# RFR24_AMS_Design_-_Microcontroller_V1.net
KiCad netlist of a schematic drawn in Altium Designer
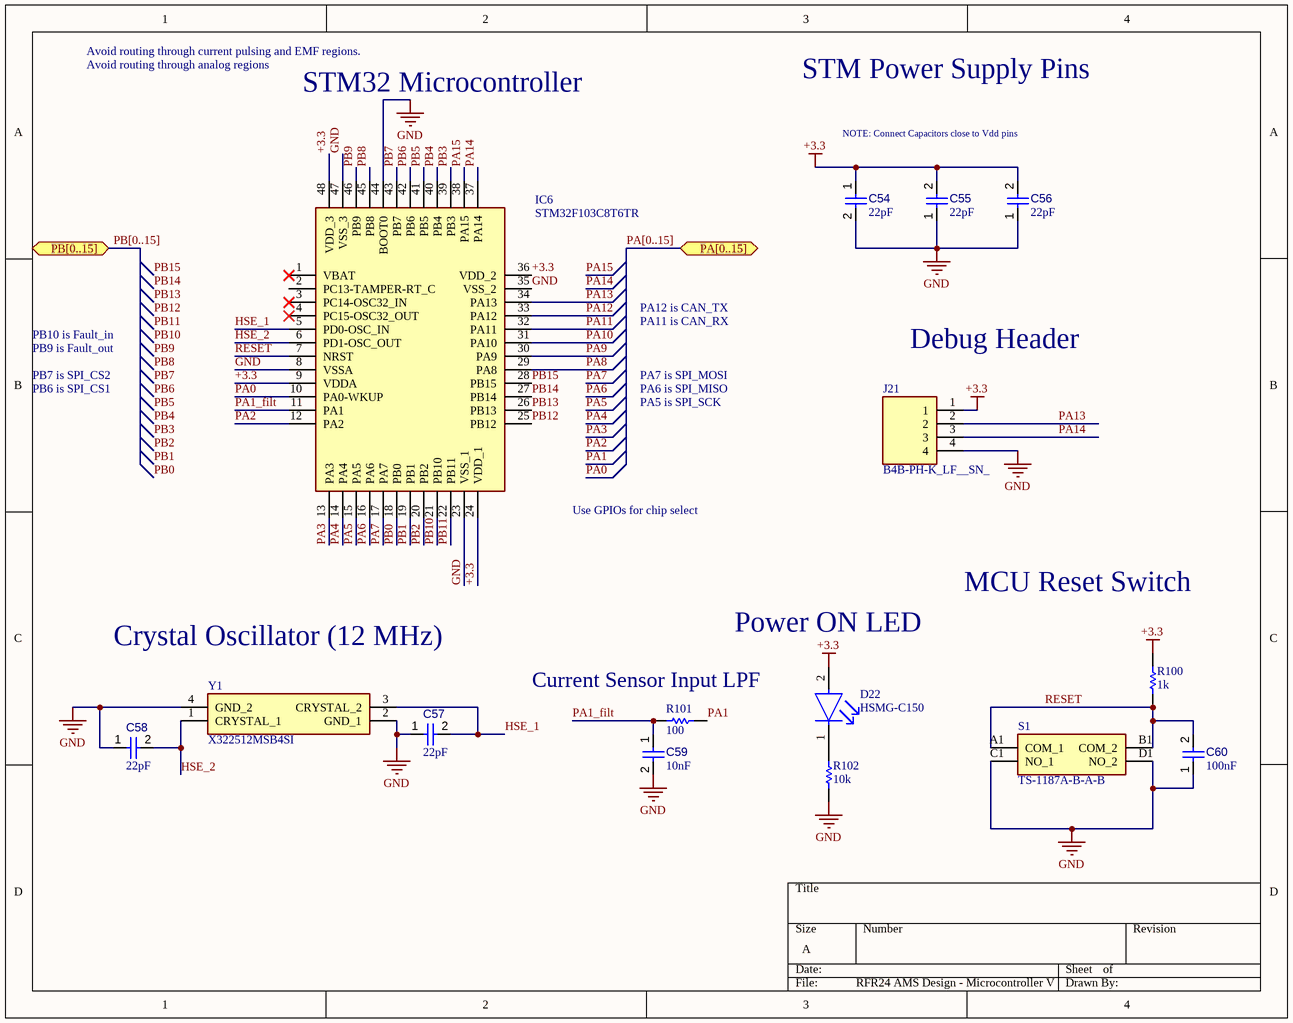
[diagram p0: RFR24 AMS Design - Microcontroller V1.SchDoc]

(export (version "E")
  (design (tool "Eeschema 10.0.6"))
  (components
    (comp (ref "C54")
      (value "22pF")
      (footprint "CAPC2013X145X50LL20T25")
      (description "Chip Capacitor, 1 uF, +/-10%, 25 V, 0805 (2012 Metric)")
      (fields (field (name "TOLERANCE") "10%") (field (name "Comment") "Capacitor 1 uF +/- 10% 25 V 0805"))
      (libsource (lib "Rutgers University") (part "CAP-NP-2"))
    )
    (comp (ref "C55")
      (value "22pF")
      (footprint "CAPC2013X145X50LL20T25")
      (description "Chip Capacitor, 1 uF, +/-10%, 25 V, 0805 (2012 Metric)")
      (fields (field (name "TOLERANCE") "10%") (field (name "Comment") "Capacitor 1 uF +/- 10% 25 V 0805"))
      (libsource (lib "Rutgers University") (part "CAP-NP-2"))
    )
    (comp (ref "C56")
      (value "22pF")
      (footprint "CAPC2013X145X50LL20T25")
      (description "Chip Capacitor, 1 uF, +/-10%, 25 V, 0805 (2012 Metric)")
      (fields (field (name "TOLERANCE") "10%") (field (name "Comment") "Capacitor 1 uF +/- 10% 25 V 0805"))
      (libsource (lib "Rutgers University") (part "CAP-NP-2"))
    )
    (comp (ref "C57")
      (value "22pF")
      (footprint "CAPC2013X145X50LL20T25")
      (description "Chip Capacitor, 1 uF, +/-10%, 25 V, 0805 (2012 Metric)")
      (fields (field (name "TOLERANCE") "10%") (field (name "Comment") "Capacitor 1 uF +/- 10% 25 V 0805"))
      (libsource (lib "Rutgers University") (part "CAP-NP-2"))
    )
    (comp (ref "C58")
      (value "22pF")
      (footprint "CAPC2013X145X50LL20T25")
      (description "Chip Capacitor, 1 uF, +/-10%, 25 V, 0805 (2012 Metric)")
      (fields (field (name "TOLERANCE") "10%") (field (name "Comment") "Capacitor 1 uF +/- 10% 25 V 0805"))
      (libsource (lib "Rutgers University") (part "CAP-NP-2"))
    )
    (comp (ref "C59")
      (value "10nF")
      (footprint "CAPC2013X145X50LL20T25")
      (description "Chip Capacitor, 1 uF, +/-10%, 25 V, 0805 (2012 Metric)")
      (fields (field (name "TOLERANCE") "10%") (field (name "Comment") "Capacitor 1 uF +/- 10% 25 V 0805"))
      (libsource (lib "Rutgers University") (part "CAP-NP-2"))
    )
    (comp (ref "C60")
      (value "100nF")
      (footprint "CAPC2013X145X50LL20T25")
      (description "Chip Capacitor, 1 uF, +/-10%, 25 V, 0805 (2012 Metric)")
      (fields (field (name "TOLERANCE") "10%") (field (name "Comment") "Capacitor 1 uF +/- 10% 25 V 0805"))
      (libsource (lib "Rutgers University") (part "CAP-NP-2"))
    )
    (comp (ref "D22")
      (value "HSMG-C150")
      (footprint "FP-HSMG-C150-MFG")
      (description "LED GREEN DIFFUSED 1206 SMD")
      (fields
        (field (name "MANUFACTURER") "Broadcom")
        (field (name "OCTOPART") "https://octopart.com/hsmg-c150-broadcom-71131304")
      )
      (libsource (lib "Altium Content Vault") (part "8706943c75ba83719d021d2fdc84c58"))
    )
    (comp (ref "IC6")
      (value "STM32F103C8T6TR")
      (footprint "SamacSys:QFP50P900X900X160-48N")
      (description "Integrated Circuit")
      (fields (field (name "MOUSER PART NUMBER") "511-STM32F103C8T6TR"))
      (libsource (lib "*") (part "STM32F103C8T6TR"))
    )
    (comp (ref "J21")
      (value "B4B-PH-K_LF__SN_")
      (footprint "SamacSys:SHDR4W50P0X200_1X4_990X450X600P")
      (description "Connector")
      (fields (field (name "MANUFACTURER_PART_NUMBER") "B4B-PH-K(LF)(SN)"))
      (libsource (lib "*") (part "B4B-PH-K_LF__SN_"))
    )
    (comp (ref "R100")
      (value "1k")
      (footprint "RESC2013X70X40LL20T20")
      (description "Chip Resistor, 1 KOhm, +/- 1%, 0.125 W, -55 to 155 degC, 0805 (2013 Metric)")
      (fields (field (name "TOLERANCE") "1%") (field (name "POWER") "125mW"))
      (libsource (lib "Rutgers University") (part "RES-2"))
    )
    (comp (ref "R101")
      (value "100")
      (footprint "RESC2013X70X40LL20T20")
      (description "Chip Resistor, 1 KOhm, +/- 1%, 0.125 W, -55 to 155 degC, 0805 (2013 Metric)")
      (fields (field (name "TOLERANCE") "1%") (field (name "POWER") "125mW"))
      (libsource (lib "Rutgers University") (part "RES-2"))
    )
    (comp (ref "R102")
      (value "10k")
      (footprint "RESC2013X70X40LL20T20")
      (description "Chip Resistor, 1 KOhm, +/- 1%, 0.125 W, -55 to 155 degC, 0805 (2013 Metric)")
      (fields (field (name "TOLERANCE") "1%") (field (name "POWER") "125mW"))
      (libsource (lib "Rutgers University") (part "RES-2"))
    )
    (comp (ref "S1")
      (value "TS-1187A-B-A-B")
      (footprint "SamacSys:TS1187ABAB")
      (description "Switch")
      (libsource (lib "*") (part "TS-1187A-B-A-B"))
    )
    (comp (ref "Y1")
      (value "X322512MSB4SI")
      (footprint "SamacSys:X322512MSB4SI")
      (description "Crystal or Oscillator")
      (libsource (lib "*") (part "X322512MSB4SI"))
    )
  )
  (nets
    (net (code "1") (name "+3.3") (class "Default")
      (node (ref "C54") (pin "1") (pinfunction "1_1") (pintype "passive"))
      (node (ref "C55") (pin "2") (pinfunction "2_2") (pintype "passive"))
      (node (ref "C56") (pin "2") (pinfunction "2_2") (pintype "passive"))
      (node (ref "D22") (pin "2") (pinfunction "A_2") (pintype "passive"))
      (node (ref "IC6") (pin "24") (pinfunction "VDD_1_24") (pintype "passive"))
      (node (ref "IC6") (pin "36") (pinfunction "VDD_2_36") (pintype "passive"))
      (node (ref "IC6") (pin "48") (pinfunction "VDD_3_48") (pintype "passive"))
      (node (ref "IC6") (pin "9") (pinfunction "VDDA_9") (pintype "passive"))
      (node (ref "J21") (pin "1") (pinfunction "1_1") (pintype "passive"))
      (node (ref "R100") (pin "2") (pinfunction "2_2") (pintype "passive"))
    )
    (net (code "2") (name "/HSE_1") (class "Default")
      (node (ref "C57") (pin "2") (pinfunction "2_2") (pintype "passive"))
      (node (ref "IC6") (pin "5") (pinfunction "PD0-OSC_IN_5") (pintype "passive"))
      (node (ref "Y1") (pin "3") (pinfunction "CRYSTAL_2_3") (pintype "passive"))
    )
    (net (code "3") (name "/HSE_2") (class "Default")
      (node (ref "C58") (pin "2") (pinfunction "2_2") (pintype "passive"))
      (node (ref "IC6") (pin "6") (pinfunction "PD1-OSC_OUT_6") (pintype "passive"))
      (node (ref "Y1") (pin "1") (pinfunction "CRYSTAL_1_1") (pintype "passive"))
    )
    (net (code "4") (name "/PA0") (class "Default")
      (node (ref "IC6") (pin "10") (pinfunction "PA0-WKUP_10") (pintype "passive"))
    )
    (net (code "5") (name "/PA1") (class "Default")
      (node (ref "R101") (pin "1") (pinfunction "1_1") (pintype "passive"))
    )
    (net (code "6") (name "/PA1_filt") (class "Default")
      (node (ref "C59") (pin "1") (pinfunction "1_1") (pintype "passive"))
      (node (ref "IC6") (pin "11") (pinfunction "PA1_11") (pintype "passive"))
      (node (ref "R101") (pin "2") (pinfunction "2_2") (pintype "passive"))
    )
    (net (code "7") (name "/PA2") (class "Default")
      (node (ref "IC6") (pin "12") (pinfunction "PA2_12") (pintype "passive"))
    )
    (net (code "8") (name "/PA3") (class "Default")
      (node (ref "IC6") (pin "13") (pinfunction "PA3_13") (pintype "passive"))
    )
    (net (code "9") (name "/PA4") (class "Default")
      (node (ref "IC6") (pin "14") (pinfunction "PA4_14") (pintype "passive"))
    )
    (net (code "10") (name "/PA5") (class "Default")
      (node (ref "IC6") (pin "15") (pinfunction "PA5_15") (pintype "passive"))
    )
    (net (code "11") (name "/PA6") (class "Default")
      (node (ref "IC6") (pin "16") (pinfunction "PA6_16") (pintype "passive"))
    )
    (net (code "12") (name "/PA7") (class "Default")
      (node (ref "IC6") (pin "17") (pinfunction "PA7_17") (pintype "passive"))
    )
    (net (code "13") (name "/PA8") (class "Default")
      (node (ref "IC6") (pin "29") (pinfunction "PA8_29") (pintype "passive"))
    )
    (net (code "14") (name "/PA9") (class "Default")
      (node (ref "IC6") (pin "30") (pinfunction "PA9_30") (pintype "passive"))
    )
    (net (code "15") (name "/PA10") (class "Default")
      (node (ref "IC6") (pin "31") (pinfunction "PA10_31") (pintype "passive"))
    )
    (net (code "16") (name "/PA11") (class "Default")
      (node (ref "IC6") (pin "32") (pinfunction "PA11_32") (pintype "passive"))
    )
    (net (code "17") (name "/PA12") (class "Default")
      (node (ref "IC6") (pin "33") (pinfunction "PA12_33") (pintype "passive"))
    )
    (net (code "18") (name "/PA13") (class "Default")
      (node (ref "IC6") (pin "34") (pinfunction "PA13_34") (pintype "passive"))
      (node (ref "J21") (pin "2") (pinfunction "2_2") (pintype "passive"))
    )
    (net (code "19") (name "/PA14") (class "Default")
      (node (ref "IC6") (pin "37") (pinfunction "PA14_37") (pintype "passive"))
      (node (ref "J21") (pin "3") (pinfunction "3_3") (pintype "passive"))
    )
    (net (code "20") (name "/PA15") (class "Default")
      (node (ref "IC6") (pin "38") (pinfunction "PA15_38") (pintype "passive"))
    )
    (net (code "22") (name "/PB0") (class "Default")
      (node (ref "IC6") (pin "18") (pinfunction "PB0_18") (pintype "passive"))
    )
    (net (code "23") (name "/PB1") (class "Default")
      (node (ref "IC6") (pin "19") (pinfunction "PB1_19") (pintype "passive"))
    )
    (net (code "24") (name "/PB2") (class "Default")
      (node (ref "IC6") (pin "20") (pinfunction "PB2_20") (pintype "passive"))
    )
    (net (code "25") (name "/PB3") (class "Default")
      (node (ref "IC6") (pin "39") (pinfunction "PB3_39") (pintype "passive"))
    )
    (net (code "26") (name "/PB4") (class "Default")
      (node (ref "IC6") (pin "40") (pinfunction "PB4_40") (pintype "passive"))
    )
    (net (code "27") (name "/PB5") (class "Default")
      (node (ref "IC6") (pin "41") (pinfunction "PB5_41") (pintype "passive"))
    )
    (net (code "28") (name "/PB6") (class "Default")
      (node (ref "IC6") (pin "42") (pinfunction "PB6_42") (pintype "passive"))
    )
    (net (code "29") (name "/PB7") (class "Default")
      (node (ref "IC6") (pin "43") (pinfunction "PB7_43") (pintype "passive"))
    )
    (net (code "30") (name "/PB8") (class "Default")
      (node (ref "IC6") (pin "45") (pinfunction "PB8_45") (pintype "passive"))
    )
    (net (code "31") (name "/PB9") (class "Default")
      (node (ref "IC6") (pin "46") (pinfunction "PB9_46") (pintype "passive"))
    )
    (net (code "32") (name "/PB10") (class "Default")
      (node (ref "IC6") (pin "21") (pinfunction "PB10_21") (pintype "passive"))
    )
    (net (code "33") (name "/PB11") (class "Default")
      (node (ref "IC6") (pin "22") (pinfunction "PB11_22") (pintype "passive"))
    )
    (net (code "34") (name "/PB12") (class "Default")
      (node (ref "IC6") (pin "25") (pinfunction "PB12_25") (pintype "passive"))
    )
    (net (code "35") (name "/PB13") (class "Default")
      (node (ref "IC6") (pin "26") (pinfunction "PB13_26") (pintype "passive"))
    )
    (net (code "36") (name "/PB14") (class "Default")
      (node (ref "IC6") (pin "27") (pinfunction "PB14_27") (pintype "passive"))
    )
    (net (code "37") (name "/PB15") (class "Default")
      (node (ref "IC6") (pin "28") (pinfunction "PB15_28") (pintype "passive"))
    )
    (net (code "39") (name "/RESET") (class "Default")
      (node (ref "C60") (pin "2") (pinfunction "2_2") (pintype "passive"))
      (node (ref "IC6") (pin "7") (pinfunction "NRST_7") (pintype "passive"))
      (node (ref "R100") (pin "1") (pinfunction "1_1") (pintype "passive"))
      (node (ref "S1") (pin "A1") (pinfunction "COM_1_A1") (pintype "passive"))
      (node (ref "S1") (pin "B1") (pinfunction "COM_2_B1") (pintype "passive"))
    )
    (net (code "40") (name "GND") (class "Default")
      (node (ref "C54") (pin "2") (pinfunction "2_2") (pintype "passive"))
      (node (ref "C55") (pin "1") (pinfunction "1_1") (pintype "passive"))
      (node (ref "C56") (pin "1") (pinfunction "1_1") (pintype "passive"))
      (node (ref "C57") (pin "1") (pinfunction "1_1") (pintype "passive"))
      (node (ref "C58") (pin "1") (pinfunction "1_1") (pintype "passive"))
      (node (ref "C59") (pin "2") (pinfunction "2_2") (pintype "passive"))
      (node (ref "C60") (pin "1") (pinfunction "1_1") (pintype "passive"))
      (node (ref "IC6") (pin "23") (pinfunction "VSS_1_23") (pintype "passive"))
      (node (ref "IC6") (pin "35") (pinfunction "VSS_2_35") (pintype "passive"))
      (node (ref "IC6") (pin "44") (pinfunction "BOOT0_44") (pintype "passive"))
      (node (ref "IC6") (pin "47") (pinfunction "VSS_3_47") (pintype "passive"))
      (node (ref "IC6") (pin "8") (pinfunction "VSSA_8") (pintype "passive"))
      (node (ref "J21") (pin "4") (pinfunction "4_4") (pintype "passive"))
      (node (ref "R102") (pin "1") (pinfunction "1_1") (pintype "passive"))
      (node (ref "S1") (pin "C1") (pinfunction "NO_1_C1") (pintype "passive"))
      (node (ref "S1") (pin "D1") (pinfunction "NO_2_D1") (pintype "passive"))
      (node (ref "Y1") (pin "2") (pinfunction "GND_1_2") (pintype "passive"))
      (node (ref "Y1") (pin "4") (pinfunction "GND_2_4") (pintype "passive"))
    )
    (net (code "41") (name "Net-(D22-C)") (class "Default")
      (node (ref "D22") (pin "1") (pinfunction "C_1") (pintype "passive"))
      (node (ref "R102") (pin "2") (pinfunction "2_2") (pintype "passive"))
    )
    (net (code "42") (name "unconnected-(IC6-PC13-TAMPER-RT_C-Pad2)") (class "Default")
      (node (ref "IC6") (pin "2") (pinfunction "PC13-TAMPER-RT_C_2") (pintype "passive"))
    )
    (net (code "43") (name "unconnected-(IC6-PC14-OSC32_IN-Pad3)") (class "Default")
      (node (ref "IC6") (pin "3") (pinfunction "PC14-OSC32_IN_3") (pintype "passive+no_connect"))
    )
    (net (code "44") (name "unconnected-(IC6-PC15-OSC32_OUT-Pad4)") (class "Default")
      (node (ref "IC6") (pin "4") (pinfunction "PC15-OSC32_OUT_4") (pintype "passive+no_connect"))
    )
    (net (code "45") (name "unconnected-(IC6-VBAT-Pad1)") (class "Default")
      (node (ref "IC6") (pin "1") (pinfunction "VBAT_1") (pintype "passive+no_connect"))
    )
  )
)
